# AD9361.net
KiCad netlist of a schematic drawn in Altium Designer
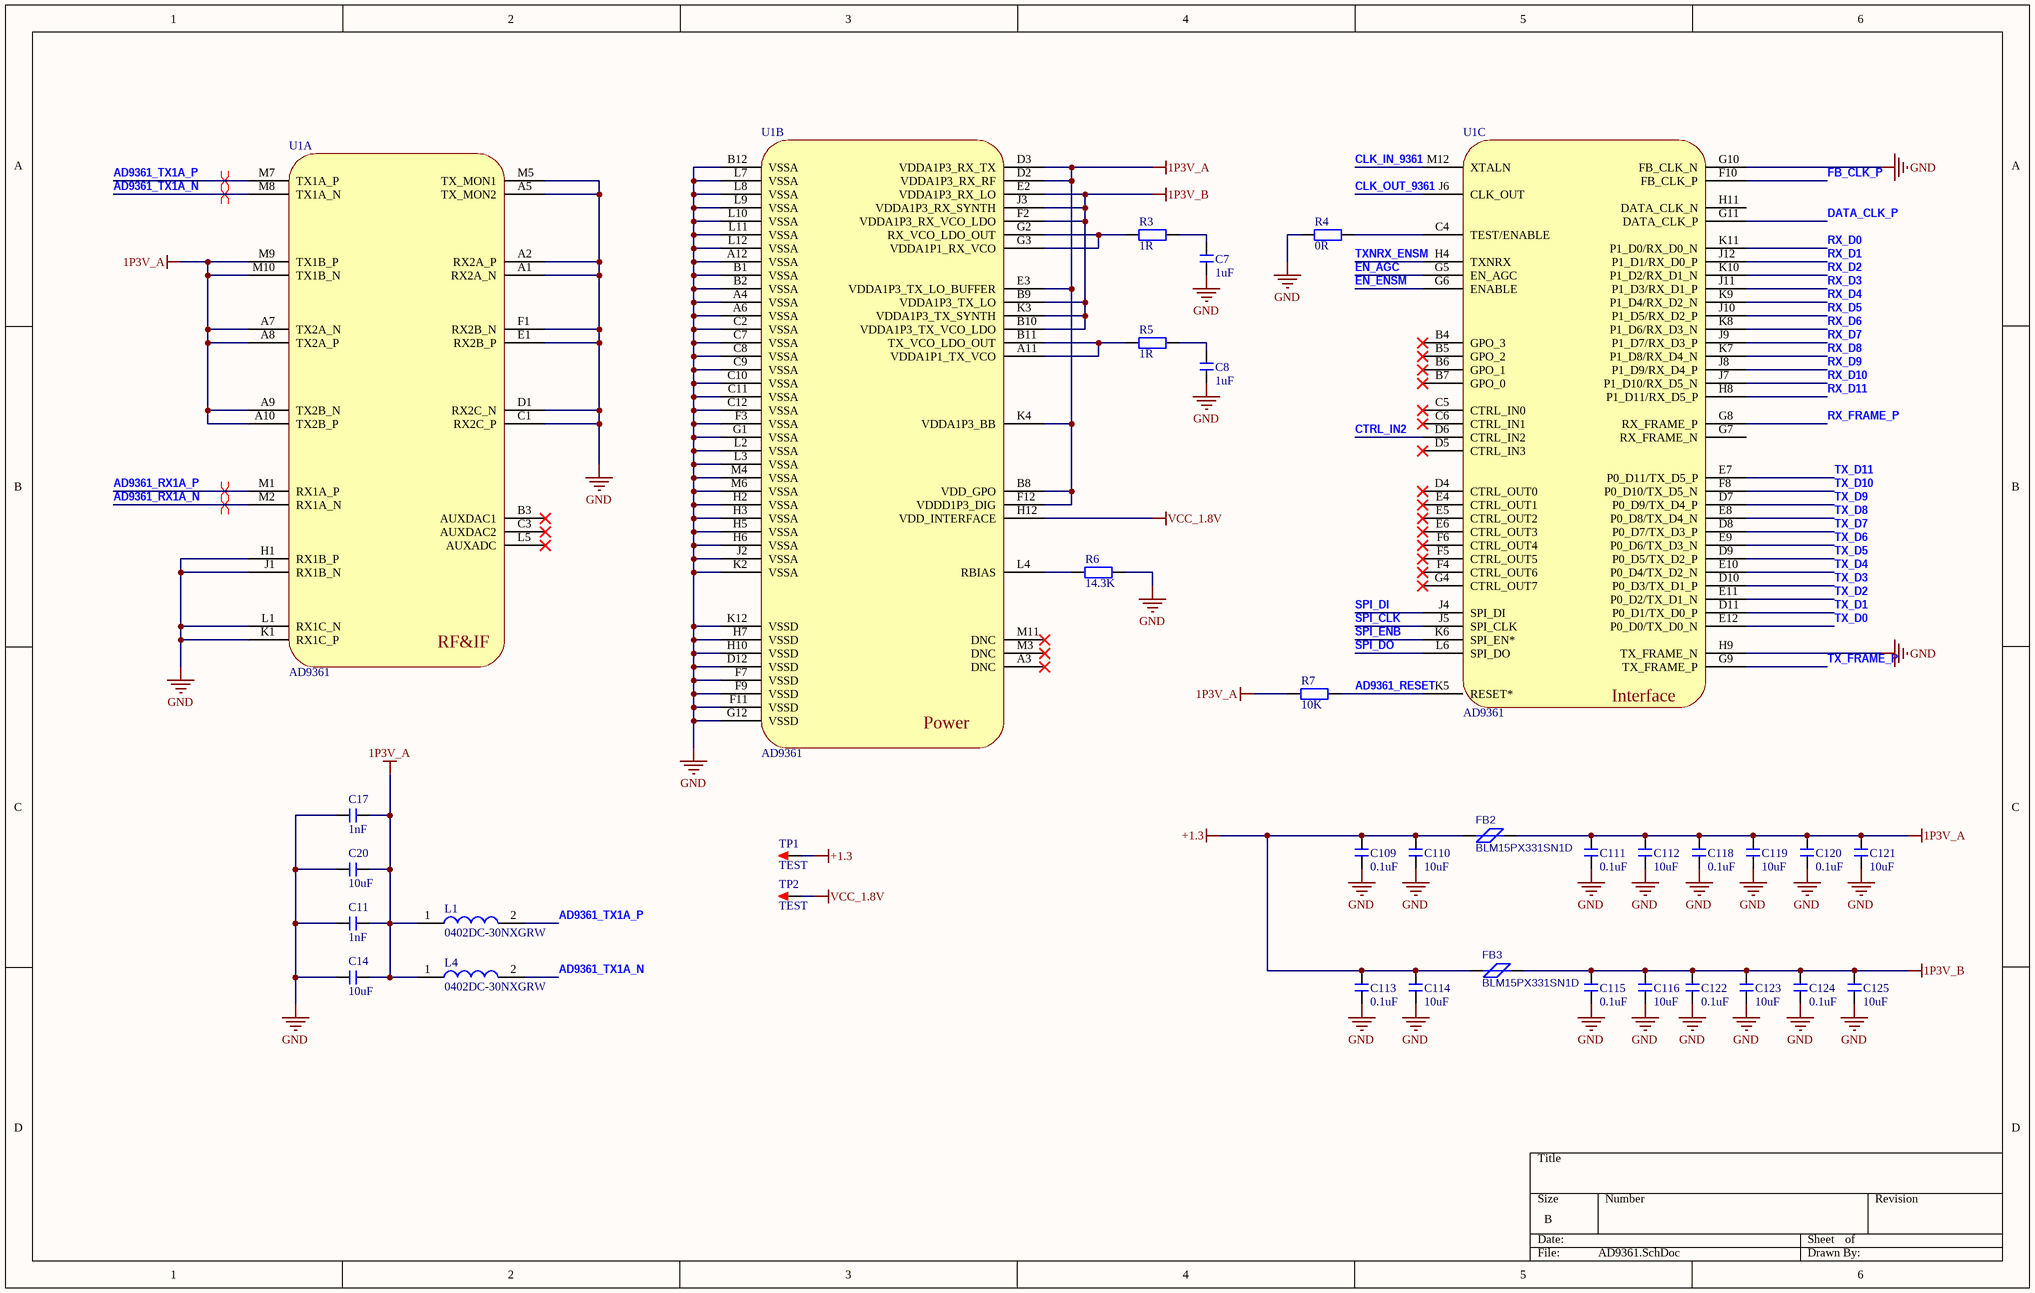
[diagram p0: AD9361.SchDoc]

(export (version "E")
  (design (tool "Eeschema 10.0.6"))
  (components
    (comp (ref "C7")
      (value "1uF")
      (footprint "SamacSys:CAP_0402")
      (description "无极性贴片电容")
      (fields (field (name "版权归属") "源创客"))
      (libsource (lib "源创客") (part "C"))
    )
    (comp (ref "C8")
      (value "1uF")
      (footprint "SamacSys:CAP_0402")
      (description "无极性贴片电容")
      (fields (field (name "版权归属") "源创客"))
      (libsource (lib "源创客") (part "C"))
    )
    (comp (ref "C11")
      (value "1nF")
      (footprint "SamacSys:CAP_0201")
      (description "无极性贴片电容")
      (fields (field (name "版权归属") "源创客"))
      (libsource (lib "源创客") (part "C"))
    )
    (comp (ref "C14")
      (value "10uF")
      (footprint "SamacSys:CAP_0402")
      (description "无极性贴片电容")
      (fields (field (name "版权归属") "源创客"))
      (libsource (lib "源创客") (part "C"))
    )
    (comp (ref "C17")
      (value "1nF")
      (footprint "SamacSys:CAP_0201")
      (description "无极性贴片电容")
      (fields (field (name "版权归属") "源创客"))
      (libsource (lib "源创客") (part "C"))
    )
    (comp (ref "C20")
      (value "10uF")
      (footprint "SamacSys:CAP_0402")
      (description "无极性贴片电容")
      (fields (field (name "版权归属") "源创客"))
      (libsource (lib "源创客") (part "C"))
    )
    (comp (ref "C109")
      (value "0.1uF")
      (footprint "SamacSys:CAP_0402")
      (description "无极性贴片电容")
      (fields (field (name "版权归属") "源创客"))
      (libsource (lib "源创客") (part "C"))
    )
    (comp (ref "C110")
      (value "10uF")
      (footprint "SamacSys:CAP_0402")
      (description "无极性贴片电容")
      (fields (field (name "版权归属") "源创客"))
      (libsource (lib "源创客") (part "C"))
    )
    (comp (ref "C111")
      (value "0.1uF")
      (footprint "SamacSys:CAP_0201")
      (description "无极性贴片电容")
      (fields (field (name "版权归属") "源创客"))
      (libsource (lib "源创客") (part "C"))
    )
    (comp (ref "C112")
      (value "10uF")
      (footprint "SamacSys:CAP_0201")
      (description "无极性贴片电容")
      (fields (field (name "版权归属") "源创客"))
      (libsource (lib "源创客") (part "C"))
    )
    (comp (ref "C113")
      (value "0.1uF")
      (footprint "SamacSys:CAP_0402")
      (description "无极性贴片电容")
      (fields (field (name "版权归属") "源创客"))
      (libsource (lib "源创客") (part "C"))
    )
    (comp (ref "C114")
      (value "10uF")
      (footprint "SamacSys:CAP_0402")
      (description "无极性贴片电容")
      (fields (field (name "版权归属") "源创客"))
      (libsource (lib "源创客") (part "C"))
    )
    (comp (ref "C115")
      (value "0.1uF")
      (footprint "SamacSys:CAP_0201")
      (description "无极性贴片电容")
      (fields (field (name "版权归属") "源创客"))
      (libsource (lib "源创客") (part "C"))
    )
    (comp (ref "C116")
      (value "10uF")
      (footprint "SamacSys:CAP_0201")
      (description "无极性贴片电容")
      (fields (field (name "版权归属") "源创客"))
      (libsource (lib "源创客") (part "C"))
    )
    (comp (ref "C118")
      (value "0.1uF")
      (footprint "SamacSys:CAP_0201")
      (description "无极性贴片电容")
      (fields (field (name "版权归属") "源创客"))
      (libsource (lib "源创客") (part "C"))
    )
    (comp (ref "C119")
      (value "10uF")
      (footprint "SamacSys:CAP_0201")
      (description "无极性贴片电容")
      (fields (field (name "版权归属") "源创客"))
      (libsource (lib "源创客") (part "C"))
    )
    (comp (ref "C120")
      (value "0.1uF")
      (footprint "SamacSys:CAP_0201")
      (description "无极性贴片电容")
      (fields (field (name "版权归属") "源创客"))
      (libsource (lib "源创客") (part "C"))
    )
    (comp (ref "C121")
      (value "10uF")
      (footprint "SamacSys:CAP_0201")
      (description "无极性贴片电容")
      (fields (field (name "版权归属") "源创客"))
      (libsource (lib "源创客") (part "C"))
    )
    (comp (ref "C122")
      (value "0.1uF")
      (footprint "SamacSys:CAP_0201")
      (description "无极性贴片电容")
      (fields (field (name "版权归属") "源创客"))
      (libsource (lib "源创客") (part "C"))
    )
    (comp (ref "C123")
      (value "10uF")
      (footprint "SamacSys:CAP_0201")
      (description "无极性贴片电容")
      (fields (field (name "版权归属") "源创客"))
      (libsource (lib "源创客") (part "C"))
    )
    (comp (ref "C124")
      (value "0.1uF")
      (footprint "SamacSys:CAP_0201")
      (description "无极性贴片电容")
      (fields (field (name "版权归属") "源创客"))
      (libsource (lib "源创客") (part "C"))
    )
    (comp (ref "C125")
      (value "10uF")
      (footprint "SamacSys:CAP_0201")
      (description "无极性贴片电容")
      (fields (field (name "版权归属") "源创客"))
      (libsource (lib "源创客") (part "C"))
    )
    (comp (ref "FB2")
      (value "BLM15PX331SN1D")
      (footprint "SamacSys:RES_0402")
      (fields (field (name "BOM_SUPPLIER PART") "C160975") (field (name "CONTRIBUTOR") "LCSC"))
      (libsource (lib "xc7k160t") (part "BLM15PX331SN1D"))
    )
    (comp (ref "FB3")
      (value "BLM15PX331SN1D")
      (footprint "SamacSys:RES_0402")
      (fields (field (name "BOM_SUPPLIER PART") "C160975") (field (name "CONTRIBUTOR") "LCSC"))
      (libsource (lib "xc7k160t") (part "BLM15PX331SN1D"))
    )
    (comp (ref "L1")
      (value "0402DC-30NXGRW")
      (footprint "0402DC SERIES")
      (description "Inductor")
      (fields
        (field (name "MANUFACTURER_PART_NUMBER") "0402DC-36NXJRW")
        (field (name "MOUSER PART NUMBER") "994-0402DC-36NXJRW")
      )
      (libsource (lib "xc7k160t") (part "0402DC-36NXJRW"))
    )
    (comp (ref "L4")
      (value "0402DC-30NXGRW")
      (footprint "0402DC SERIES")
      (description "Inductor")
      (fields
        (field (name "MANUFACTURER_PART_NUMBER") "0402DC-36NXJRW")
        (field (name "MOUSER PART NUMBER") "994-0402DC-36NXJRW")
      )
      (libsource (lib "xc7k160t") (part "0402DC-36NXJRW"))
    )
    (comp (ref "R3")
      (value "1R")
      (footprint "SamacSys:RES_0201")
      (description "Resistor")
      (libsource (lib "源创客") (part "Resistor"))
    )
    (comp (ref "R4")
      (value "0R")
      (footprint "SamacSys:RES_0201")
      (description "Resistor")
      (libsource (lib "源创客") (part "Resistor"))
    )
    (comp (ref "R5")
      (value "1R")
      (footprint "SamacSys:RES_0402")
      (description "Resistor")
      (libsource (lib "源创客") (part "Resistor"))
    )
    (comp (ref "R6")
      (value "14.3K")
      (footprint "SamacSys:RES_0402")
      (description "Resistor")
      (libsource (lib "源创客") (part "Resistor"))
    )
    (comp (ref "R7")
      (value "10K")
      (footprint "SamacSys:RES_0201")
      (description "Resistor")
      (libsource (lib "源创客") (part "Resistor"))
    )
    (comp (ref "TP1")
      (value "TEST")
      (footprint "TEST 0.8")
      (description "测试点")
      (fields (field (name "版权归属") "源创客"))
      (libsource (lib "源创客") (part "TEST"))
    )
    (comp (ref "TP2")
      (value "TEST")
      (footprint "TEST 0.8")
      (description "测试点")
      (fields (field (name "版权归属") "源创客"))
      (libsource (lib "源创客") (part "TEST"))
    )
    (comp (ref "U1") (value "AD9361") (footprint "AD936X") (libsource (lib "xc7k160t") (part "AD9363")))
  )
  (nets
    (net (code "1") (name "+1.3") (class "Default")
      (node (ref "C109") (pin "1") (pinfunction "1_1") (pintype "passive"))
      (node (ref "C110") (pin "2") (pinfunction "2_2") (pintype "passive"))
      (node (ref "C113") (pin "1") (pinfunction "1_1") (pintype "passive"))
      (node (ref "C114") (pin "2") (pinfunction "2_2") (pintype "passive"))
      (node (ref "FB2") (pin "1") (pinfunction "1_1") (pintype "passive"))
      (node (ref "FB3") (pin "1") (pinfunction "1_1") (pintype "passive"))
      (node (ref "TP1") (pin "1") (pinfunction "1_1") (pintype "passive"))
    )
    (net (code "2") (name "/AD9361_RESET") (class "Default")
      (node (ref "R7") (pin "1") (pinfunction "1_1") (pintype "passive"))
      (node (ref "U1") (pin "K5") (pinfunction "RESET*_K5") (pintype "passive"))
    )
    (net (code "3") (name "/AD9361_RX1A_N") (class "Default")
      (node (ref "U1") (pin "M2") (pinfunction "RX1A_N_M2") (pintype "passive"))
    )
    (net (code "4") (name "/AD9361_RX1A_P") (class "Default")
      (node (ref "U1") (pin "M1") (pinfunction "RX1A_P_M1") (pintype "passive"))
    )
    (net (code "5") (name "/AD9361_TX1A_N") (class "Default")
      (node (ref "L4") (pin "2") (pinfunction "2_2") (pintype "passive"))
      (node (ref "U1") (pin "M8") (pinfunction "TX1A_N_M8") (pintype "passive"))
    )
    (net (code "6") (name "/AD9361_TX1A_P") (class "Default")
      (node (ref "L1") (pin "2") (pinfunction "2_2") (pintype "passive"))
      (node (ref "U1") (pin "M7") (pinfunction "TX1A_P_M7") (pintype "passive"))
    )
    (net (code "7") (name "/CLK_IN_9361") (class "Default")
      (node (ref "U1") (pin "M12") (pinfunction "XTALN_M12") (pintype "passive"))
    )
    (net (code "8") (name "/CLK_OUT_9361") (class "Default")
      (node (ref "U1") (pin "J6") (pinfunction "CLK_OUT_J6") (pintype "passive"))
    )
    (net (code "9") (name "/CTRL_IN2") (class "Default")
      (node (ref "U1") (pin "D6") (pinfunction "CTRL_IN2_D6") (pintype "passive"))
    )
    (net (code "10") (name "/DATA_CLK_P") (class "Default")
      (node (ref "U1") (pin "G11") (pinfunction "DATA_CLK_P_G11") (pintype "passive"))
    )
    (net (code "11") (name "/EN_AGC") (class "Default")
      (node (ref "U1") (pin "G5") (pinfunction "EN_AGC_G5") (pintype "passive"))
    )
    (net (code "12") (name "/EN_ENSM") (class "Default")
      (node (ref "U1") (pin "G6") (pinfunction "ENABLE_G6") (pintype "passive"))
    )
    (net (code "13") (name "/FB_CLK_P") (class "Default")
      (node (ref "U1") (pin "F10") (pinfunction "FB_CLK_P_F10") (pintype "passive"))
    )
    (net (code "14") (name "/RX_D0") (class "Default")
      (node (ref "U1") (pin "K11") (pinfunction "P1_D0/RX_D0_N_K11") (pintype "passive"))
    )
    (net (code "15") (name "/RX_D1") (class "Default")
      (node (ref "U1") (pin "J12") (pinfunction "P1_D1/RX_D0_P_J12") (pintype "passive"))
    )
    (net (code "16") (name "/RX_D2") (class "Default")
      (node (ref "U1") (pin "K10") (pinfunction "P1_D2/RX_D1_N_K10") (pintype "passive"))
    )
    (net (code "17") (name "/RX_D3") (class "Default")
      (node (ref "U1") (pin "J11") (pinfunction "P1_D3/RX_D1_P_J11") (pintype "passive"))
    )
    (net (code "18") (name "/RX_D4") (class "Default")
      (node (ref "U1") (pin "K9") (pinfunction "P1_D4/RX_D2_N_K9") (pintype "passive"))
    )
    (net (code "19") (name "/RX_D5") (class "Default")
      (node (ref "U1") (pin "J10") (pinfunction "P1_D5/RX_D2_P_J10") (pintype "passive"))
    )
    (net (code "20") (name "/RX_D6") (class "Default")
      (node (ref "U1") (pin "K8") (pinfunction "P1_D6/RX_D3_N_K8") (pintype "passive"))
    )
    (net (code "21") (name "/RX_D7") (class "Default")
      (node (ref "U1") (pin "J9") (pinfunction "P1_D7/RX_D3_P_J9") (pintype "passive"))
    )
    (net (code "22") (name "/RX_D8") (class "Default")
      (node (ref "U1") (pin "K7") (pinfunction "P1_D8/RX_D4_N_K7") (pintype "passive"))
    )
    (net (code "23") (name "/RX_D9") (class "Default")
      (node (ref "U1") (pin "J8") (pinfunction "P1_D9/RX_D4_P_J8") (pintype "passive"))
    )
    (net (code "24") (name "/RX_D10") (class "Default")
      (node (ref "U1") (pin "J7") (pinfunction "P1_D10/RX_D5_N_J7") (pintype "passive"))
    )
    (net (code "25") (name "/RX_D11") (class "Default")
      (node (ref "U1") (pin "H8") (pinfunction "P1_D11/RX_D5_P_H8") (pintype "passive"))
    )
    (net (code "26") (name "/RX_FRAME_P") (class "Default")
      (node (ref "U1") (pin "G8") (pinfunction "RX_FRAME_P_G8") (pintype "passive"))
    )
    (net (code "27") (name "/SPI_CLK") (class "Default")
      (node (ref "U1") (pin "J5") (pinfunction "SPI_CLK_J5") (pintype "passive"))
    )
    (net (code "28") (name "/SPI_DI") (class "Default")
      (node (ref "U1") (pin "J4") (pinfunction "SPI_DI_J4") (pintype "passive"))
    )
    (net (code "29") (name "/SPI_DO") (class "Default")
      (node (ref "U1") (pin "L6") (pinfunction "SPI_DO_L6") (pintype "passive"))
    )
    (net (code "30") (name "/SPI_ENB") (class "Default")
      (node (ref "U1") (pin "K6") (pinfunction "SPI_EN*_K6") (pintype "passive"))
    )
    (net (code "31") (name "/TXNRX_ENSM") (class "Default")
      (node (ref "U1") (pin "H4") (pinfunction "TXNRX_H4") (pintype "passive"))
    )
    (net (code "32") (name "/TX_D0") (class "Default")
      (node (ref "U1") (pin "E12") (pinfunction "P0_D0/TX_D0_N_E12") (pintype "passive"))
    )
    (net (code "33") (name "/TX_D1") (class "Default")
      (node (ref "U1") (pin "D11") (pinfunction "P0_D1/TX_D0_P_D11") (pintype "passive"))
    )
    (net (code "34") (name "/TX_D2") (class "Default")
      (node (ref "U1") (pin "E11") (pinfunction "P0_D2/TX_D1_N_E11") (pintype "passive"))
    )
    (net (code "35") (name "/TX_D3") (class "Default")
      (node (ref "U1") (pin "D10") (pinfunction "P0_D3/TX_D1_P_D10") (pintype "passive"))
    )
    (net (code "36") (name "/TX_D4") (class "Default")
      (node (ref "U1") (pin "E10") (pinfunction "P0_D4/TX_D2_N_E10") (pintype "passive"))
    )
    (net (code "37") (name "/TX_D5") (class "Default")
      (node (ref "U1") (pin "D9") (pinfunction "P0_D5/TX_D2_P_D9") (pintype "passive"))
    )
    (net (code "38") (name "/TX_D6") (class "Default")
      (node (ref "U1") (pin "E9") (pinfunction "P0_D6/TX_D3_N_E9") (pintype "passive"))
    )
    (net (code "39") (name "/TX_D7") (class "Default")
      (node (ref "U1") (pin "D8") (pinfunction "P0_D7/TX_D3_P_D8") (pintype "passive"))
    )
    (net (code "40") (name "/TX_D8") (class "Default")
      (node (ref "U1") (pin "E8") (pinfunction "P0_D8/TX_D4_N_E8") (pintype "passive"))
    )
    (net (code "41") (name "/TX_D9") (class "Default")
      (node (ref "U1") (pin "D7") (pinfunction "P0_D9/TX_D4_P_D7") (pintype "passive"))
    )
    (net (code "42") (name "/TX_D10") (class "Default")
      (node (ref "U1") (pin "F8") (pinfunction "P0_D10/TX_D5_N_F8") (pintype "passive"))
    )
    (net (code "43") (name "/TX_D11") (class "Default")
      (node (ref "U1") (pin "E7") (pinfunction "P0_D11/TX_D5_P_E7") (pintype "passive"))
    )
    (net (code "44") (name "/TX_FRAME_P") (class "Default")
      (node (ref "U1") (pin "G9") (pinfunction "TX_FRAME_P_G9") (pintype "passive"))
    )
    (net (code "45") (name "1P3V_A") (class "Default")
      (node (ref "C11") (pin "2") (pinfunction "2_2") (pintype "passive"))
      (node (ref "C111") (pin "1") (pinfunction "1_1") (pintype "passive"))
      (node (ref "C112") (pin "2") (pinfunction "2_2") (pintype "passive"))
      (node (ref "C118") (pin "1") (pinfunction "1_1") (pintype "passive"))
      (node (ref "C119") (pin "2") (pinfunction "2_2") (pintype "passive"))
      (node (ref "C120") (pin "1") (pinfunction "1_1") (pintype "passive"))
      (node (ref "C121") (pin "2") (pinfunction "2_2") (pintype "passive"))
      (node (ref "C14") (pin "2") (pinfunction "2_2") (pintype "passive"))
      (node (ref "C17") (pin "2") (pinfunction "2_2") (pintype "passive"))
      (node (ref "C20") (pin "2") (pinfunction "2_2") (pintype "passive"))
      (node (ref "FB2") (pin "2") (pinfunction "2_2") (pintype "passive"))
      (node (ref "L1") (pin "1") (pinfunction "1_1") (pintype "passive"))
      (node (ref "L4") (pin "1") (pinfunction "1_1") (pintype "passive"))
      (node (ref "R7") (pin "2") (pinfunction "2_2") (pintype "passive"))
      (node (ref "U1") (pin "A10") (pinfunction "TX2B_P_A10") (pintype "passive"))
      (node (ref "U1") (pin "A7") (pinfunction "TX2A_N_A7") (pintype "passive"))
      (node (ref "U1") (pin "A8") (pinfunction "TX2A_P_A8") (pintype "passive"))
      (node (ref "U1") (pin "A9") (pinfunction "TX2B_N_A9") (pintype "passive"))
      (node (ref "U1") (pin "B8") (pinfunction "VDD_GPO_B8") (pintype "passive"))
      (node (ref "U1") (pin "D2") (pinfunction "VDDA1P3_RX_RF_D2") (pintype "passive"))
      (node (ref "U1") (pin "D3") (pinfunction "VDDA1P3_RX_TX_D3") (pintype "passive"))
      (node (ref "U1") (pin "E3") (pinfunction "VDDA1P3_TX_LO_BUFFER_E3") (pintype "passive"))
      (node (ref "U1") (pin "F12") (pinfunction "VDDD1P3_DIG_F12") (pintype "passive"))
      (node (ref "U1") (pin "K4") (pinfunction "VDDA1P3_BB_K4") (pintype "passive"))
      (node (ref "U1") (pin "M10") (pinfunction "TX1B_N_M10") (pintype "passive"))
      (node (ref "U1") (pin "M9") (pinfunction "TX1B_P_M9") (pintype "passive"))
    )
    (net (code "46") (name "1P3V_B") (class "Default")
      (node (ref "C115") (pin "1") (pinfunction "1_1") (pintype "passive"))
      (node (ref "C116") (pin "2") (pinfunction "2_2") (pintype "passive"))
      (node (ref "C122") (pin "1") (pinfunction "1_1") (pintype "passive"))
      (node (ref "C123") (pin "2") (pinfunction "2_2") (pintype "passive"))
      (node (ref "C124") (pin "1") (pinfunction "1_1") (pintype "passive"))
      (node (ref "C125") (pin "2") (pinfunction "2_2") (pintype "passive"))
      (node (ref "FB3") (pin "2") (pinfunction "2_2") (pintype "passive"))
      (node (ref "U1") (pin "B10") (pinfunction "VDDA1P3_TX_VCO_LDO_B10") (pintype "passive"))
      (node (ref "U1") (pin "B9") (pinfunction "VDDA1P3_TX_LO_B9") (pintype "passive"))
      (node (ref "U1") (pin "E2") (pinfunction "VDDA1P3_RX_LO_E2") (pintype "passive"))
      (node (ref "U1") (pin "F2") (pinfunction "VDDA1P3_RX_VCO_LDO_F2") (pintype "passive"))
      (node (ref "U1") (pin "J3") (pinfunction "VDDA1P3_RX_SYNTH_J3") (pintype "passive"))
      (node (ref "U1") (pin "K3") (pinfunction "VDDA1P3_TX_SYNTH_K3") (pintype "passive"))
    )
    (net (code "47") (name "GND") (class "Default")
      (node (ref "C109") (pin "2") (pinfunction "2_2") (pintype "passive"))
      (node (ref "C11") (pin "1") (pinfunction "1_1") (pintype "passive"))
      (node (ref "C110") (pin "1") (pinfunction "1_1") (pintype "passive"))
      (node (ref "C111") (pin "2") (pinfunction "2_2") (pintype "passive"))
      (node (ref "C112") (pin "1") (pinfunction "1_1") (pintype "passive"))
      (node (ref "C113") (pin "2") (pinfunction "2_2") (pintype "passive"))
      (node (ref "C114") (pin "1") (pinfunction "1_1") (pintype "passive"))
      (node (ref "C115") (pin "2") (pinfunction "2_2") (pintype "passive"))
      (node (ref "C116") (pin "1") (pinfunction "1_1") (pintype "passive"))
      (node (ref "C118") (pin "2") (pinfunction "2_2") (pintype "passive"))
      (node (ref "C119") (pin "1") (pinfunction "1_1") (pintype "passive"))
      (node (ref "C120") (pin "2") (pinfunction "2_2") (pintype "passive"))
      (node (ref "C121") (pin "1") (pinfunction "1_1") (pintype "passive"))
      (node (ref "C122") (pin "2") (pinfunction "2_2") (pintype "passive"))
      (node (ref "C123") (pin "1") (pinfunction "1_1") (pintype "passive"))
      (node (ref "C124") (pin "2") (pinfunction "2_2") (pintype "passive"))
      (node (ref "C125") (pin "1") (pinfunction "1_1") (pintype "passive"))
      (node (ref "C14") (pin "1") (pinfunction "1_1") (pintype "passive"))
      (node (ref "C17") (pin "1") (pinfunction "1_1") (pintype "passive"))
      (node (ref "C20") (pin "1") (pinfunction "1_1") (pintype "passive"))
      (node (ref "C7") (pin "1") (pinfunction "1_1") (pintype "passive"))
      (node (ref "C8") (pin "1") (pinfunction "1_1") (pintype "passive"))
      (node (ref "R4") (pin "2") (pinfunction "2_2") (pintype "passive"))
      (node (ref "R6") (pin "1") (pinfunction "1_1") (pintype "passive"))
      (node (ref "U1") (pin "A1") (pinfunction "RX2A_N_A1") (pintype "passive"))
      (node (ref "U1") (pin "A12") (pinfunction "VSSA_A12") (pintype "passive"))
      (node (ref "U1") (pin "A2") (pinfunction "RX2A_P_A2") (pintype "passive"))
      (node (ref "U1") (pin "A4") (pinfunction "VSSA_A4") (pintype "passive"))
      (node (ref "U1") (pin "A5") (pinfunction "TX_MON2_A5") (pintype "passive"))
      (node (ref "U1") (pin "A6") (pinfunction "VSSA_A6") (pintype "passive"))
      (node (ref "U1") (pin "B1") (pinfunction "VSSA_B1") (pintype "passive"))
      (node (ref "U1") (pin "B12") (pinfunction "VSSA_B12") (pintype "passive"))
      (node (ref "U1") (pin "B2") (pinfunction "VSSA_B2") (pintype "passive"))
      (node (ref "U1") (pin "C1") (pinfunction "RX2C_P_C1") (pintype "passive"))
      (node (ref "U1") (pin "C10") (pinfunction "VSSA_C10") (pintype "passive"))
      (node (ref "U1") (pin "C11") (pinfunction "VSSA_C11") (pintype "passive"))
      (node (ref "U1") (pin "C12") (pinfunction "VSSA_C12") (pintype "passive"))
      (node (ref "U1") (pin "C2") (pinfunction "VSSA_C2") (pintype "passive"))
      (node (ref "U1") (pin "C7") (pinfunction "VSSA_C7") (pintype "passive"))
      (node (ref "U1") (pin "C8") (pinfunction "VSSA_C8") (pintype "passive"))
      (node (ref "U1") (pin "C9") (pinfunction "VSSA_C9") (pintype "passive"))
      (node (ref "U1") (pin "D1") (pinfunction "RX2C_N_D1") (pintype "passive"))
      (node (ref "U1") (pin "D12") (pinfunction "VSSD_D12") (pintype "passive"))
      (node (ref "U1") (pin "E1") (pinfunction "RX2B_P_E1") (pintype "passive"))
      (node (ref "U1") (pin "F1") (pinfunction "RX2B_N_F1") (pintype "passive"))
      (node (ref "U1") (pin "F11") (pinfunction "VSSD_F11") (pintype "passive"))
      (node (ref "U1") (pin "F3") (pinfunction "VSSA_F3") (pintype "passive"))
      (node (ref "U1") (pin "F7") (pinfunction "VSSD_F7") (pintype "passive"))
      (node (ref "U1") (pin "F9") (pinfunction "VSSD_F9") (pintype "passive"))
      (node (ref "U1") (pin "G1") (pinfunction "VSSA_G1") (pintype "passive"))
      (node (ref "U1") (pin "G10") (pinfunction "FB_CLK_N_G10") (pintype "passive"))
      (node (ref "U1") (pin "G12") (pinfunction "VSSD_G12") (pintype "passive"))
      (node (ref "U1") (pin "H1") (pinfunction "RX1B_P_H1") (pintype "passive"))
      (node (ref "U1") (pin "H10") (pinfunction "VSSD_H10") (pintype "passive"))
      (node (ref "U1") (pin "H2") (pinfunction "VSSA_H2") (pintype "passive"))
      (node (ref "U1") (pin "H3") (pinfunction "VSSA_H3") (pintype "passive"))
      (node (ref "U1") (pin "H5") (pinfunction "VSSA_H5") (pintype "passive"))
      (node (ref "U1") (pin "H6") (pinfunction "VSSA_H6") (pintype "passive"))
      (node (ref "U1") (pin "H7") (pinfunction "VSSD_H7") (pintype "passive"))
      (node (ref "U1") (pin "H9") (pinfunction "TX_FRAME_N_H9") (pintype "passive"))
      (node (ref "U1") (pin "J1") (pinfunction "RX1B_N_J1") (pintype "passive"))
      (node (ref "U1") (pin "J2") (pinfunction "VSSA_J2") (pintype "passive"))
      (node (ref "U1") (pin "K1") (pinfunction "RX1C_P_K1") (pintype "passive"))
      (node (ref "U1") (pin "K12") (pinfunction "VSSD_K12") (pintype "passive"))
      (node (ref "U1") (pin "K2") (pinfunction "VSSA_K2") (pintype "passive"))
      (node (ref "U1") (pin "L1") (pinfunction "RX1C_N_L1") (pintype "passive"))
      (node (ref "U1") (pin "L10") (pinfunction "VSSA_L10") (pintype "passive"))
      (node (ref "U1") (pin "L11") (pinfunction "VSSA_L11") (pintype "passive"))
      (node (ref "U1") (pin "L12") (pinfunction "VSSA_L12") (pintype "passive"))
      (node (ref "U1") (pin "L2") (pinfunction "VSSA_L2") (pintype "passive"))
      (node (ref "U1") (pin "L3") (pinfunction "VSSA_L3") (pintype "passive"))
      (node (ref "U1") (pin "L7") (pinfunction "VSSA_L7") (pintype "passive"))
      (node (ref "U1") (pin "L8") (pinfunction "VSSA_L8") (pintype "passive"))
      (node (ref "U1") (pin "L9") (pinfunction "VSSA_L9") (pintype "passive"))
      (node (ref "U1") (pin "M4") (pinfunction "VSSA_M4") (pintype "passive"))
      (node (ref "U1") (pin "M5") (pinfunction "TX_MON1_M5") (pintype "passive"))
      (node (ref "U1") (pin "M6") (pinfunction "VSSA_M6") (pintype "passive"))
    )
    (net (code "48") (name "Net-(C7-Pad2)") (class "Default")
      (node (ref "C7") (pin "2") (pinfunction "2_2") (pintype "passive"))
      (node (ref "R3") (pin "1") (pinfunction "1_1") (pintype "passive"))
    )
    (net (code "49") (name "Net-(C8-Pad2)") (class "Default")
      (node (ref "C8") (pin "2") (pinfunction "2_2") (pintype "passive"))
      (node (ref "R5") (pin "1") (pinfunction "1_1") (pintype "passive"))
    )
    (net (code "50") (name "Net-(U1B-RBIAS)") (class "Default")
      (node (ref "R6") (pin "2") (pinfunction "2_2") (pintype "passive"))
      (node (ref "U1") (pin "L4") (pinfunction "RBIAS_L4") (pintype "passive"))
    )
    (net (code "51") (name "Net-(U1B-RX_VCO_LDO_OUT)") (class "Default")
      (node (ref "R3") (pin "2") (pinfunction "2_2") (pintype "passive"))
      (node (ref "U1") (pin "G2") (pinfunction "RX_VCO_LDO_OUT_G2") (pintype "passive"))
      (node (ref "U1") (pin "G3") (pinfunction "VDDA1P1_RX_VCO_G3") (pintype "passive"))
    )
    (net (code "52") (name "Net-(U1B-TX_VCO_LDO_OUT)") (class "Default")
      (node (ref "R5") (pin "2") (pinfunction "2_2") (pintype "passive"))
      (node (ref "U1") (pin "A11") (pinfunction "VDDA1P1_TX_VCO_A11") (pintype "passive"))
      (node (ref "U1") (pin "B11") (pinfunction "TX_VCO_LDO_OUT_B11") (pintype "passive"))
    )
    (net (code "53") (name "Net-(U1C-TEST{slash}ENABLE)") (class "Default")
      (node (ref "R4") (pin "1") (pinfunction "1_1") (pintype "passive"))
      (node (ref "U1") (pin "C4") (pinfunction "TEST/ENABLE_C4") (pintype "passive"))
    )
    (net (code "54") (name "VCC_1.8V") (class "Default")
      (node (ref "TP2") (pin "1") (pinfunction "1_1") (pintype "passive"))
      (node (ref "U1") (pin "H12") (pinfunction "VDD_INTERFACE_H12") (pintype "passive"))
    )
    (net (code "55") (name "unconnected-(U1A-AUXADC-PadL5)") (class "Default")
      (node (ref "U1") (pin "L5") (pinfunction "AUXADC_L5") (pintype "passive+no_connect"))
    )
    (net (code "56") (name "unconnected-(U1A-AUXDAC1-PadB3)") (class "Default")
      (node (ref "U1") (pin "B3") (pinfunction "AUXDAC1_B3") (pintype "passive+no_connect"))
    )
    (net (code "57") (name "unconnected-(U1A-AUXDAC2-PadC3)") (class "Default")
      (node (ref "U1") (pin "C3") (pinfunction "AUXDAC2_C3") (pintype "passive+no_connect"))
    )
    (net (code "58") (name "unconnected-(U1B-DNC-PadA3)") (class "Default")
      (node (ref "U1") (pin "A3") (pinfunction "DNC_A3") (pintype "passive+no_connect"))
    )
    (net (code "59") (name "unconnected-(U1B-DNC-PadM3)") (class "Default")
      (node (ref "U1") (pin "M3") (pinfunction "DNC_M3") (pintype "passive+no_connect"))
    )
    (net (code "60") (name "unconnected-(U1B-DNC-PadM11)") (class "Default")
      (node (ref "U1") (pin "M11") (pinfunction "DNC_M11") (pintype "passive+no_connect"))
    )
    (net (code "61") (name "unconnected-(U1C-CTRL_IN0-PadC5)") (class "Default")
      (node (ref "U1") (pin "C5") (pinfunction "CTRL_IN0_C5") (pintype "passive+no_connect"))
    )
    (net (code "62") (name "unconnected-(U1C-CTRL_IN1-PadC6)") (class "Default")
      (node (ref "U1") (pin "C6") (pinfunction "CTRL_IN1_C6") (pintype "passive+no_connect"))
    )
    (net (code "63") (name "unconnected-(U1C-CTRL_IN3-PadD5)") (class "Default")
      (node (ref "U1") (pin "D5") (pinfunction "CTRL_IN3_D5") (pintype "passive+no_connect"))
    )
    (net (code "64") (name "unconnected-(U1C-CTRL_OUT0-PadD4)") (class "Default")
      (node (ref "U1") (pin "D4") (pinfunction "CTRL_OUT0_D4") (pintype "passive+no_connect"))
    )
    (net (code "65") (name "unconnected-(U1C-CTRL_OUT1-PadE4)") (class "Default")
      (node (ref "U1") (pin "E4") (pinfunction "CTRL_OUT1_E4") (pintype "passive+no_connect"))
    )
    (net (code "66") (name "unconnected-(U1C-CTRL_OUT2-PadE5)") (class "Default")
      (node (ref "U1") (pin "E5") (pinfunction "CTRL_OUT2_E5") (pintype "passive+no_connect"))
    )
    (net (code "67") (name "unconnected-(U1C-CTRL_OUT3-PadE6)") (class "Default")
      (node (ref "U1") (pin "E6") (pinfunction "CTRL_OUT3_E6") (pintype "passive+no_connect"))
    )
    (net (code "68") (name "unconnected-(U1C-CTRL_OUT4-PadF6)") (class "Default")
      (node (ref "U1") (pin "F6") (pinfunction "CTRL_OUT4_F6") (pintype "passive+no_connect"))
    )
    (net (code "69") (name "unconnected-(U1C-CTRL_OUT5-PadF5)") (class "Default")
      (node (ref "U1") (pin "F5") (pinfunction "CTRL_OUT5_F5") (pintype "passive+no_connect"))
    )
    (net (code "70") (name "unconnected-(U1C-CTRL_OUT6-PadF4)") (class "Default")
      (node (ref "U1") (pin "F4") (pinfunction "CTRL_OUT6_F4") (pintype "passive+no_connect"))
    )
    (net (code "71") (name "unconnected-(U1C-CTRL_OUT7-PadG4)") (class "Default")
      (node (ref "U1") (pin "G4") (pinfunction "CTRL_OUT7_G4") (pintype "passive+no_connect"))
    )
    (net (code "72") (name "unconnected-(U1C-DATA_CLK_N-PadH11)") (class "Default")
      (node (ref "U1") (pin "H11") (pinfunction "DATA_CLK_N_H11") (pintype "passive"))
    )
    (net (code "73") (name "unconnected-(U1C-GPO_0-PadB7)") (class "Default")
      (node (ref "U1") (pin "B7") (pinfunction "GPO_0_B7") (pintype "passive+no_connect"))
    )
    (net (code "74") (name "unconnected-(U1C-GPO_1-PadB6)") (class "Default")
      (node (ref "U1") (pin "B6") (pinfunction "GPO_1_B6") (pintype "passive+no_connect"))
    )
    (net (code "75") (name "unconnected-(U1C-GPO_2-PadB5)") (class "Default")
      (node (ref "U1") (pin "B5") (pinfunction "GPO_2_B5") (pintype "passive+no_connect"))
    )
    (net (code "76") (name "unconnected-(U1C-GPO_3-PadB4)") (class "Default")
      (node (ref "U1") (pin "B4") (pinfunction "GPO_3_B4") (pintype "passive+no_connect"))
    )
    (net (code "77") (name "unconnected-(U1C-RX_FRAME_N-PadG7)") (class "Default")
      (node (ref "U1") (pin "G7") (pinfunction "RX_FRAME_N_G7") (pintype "passive"))
    )
  )
)
